# IF_Supply.net
KiCad netlist of a schematic drawn in Altium Designer
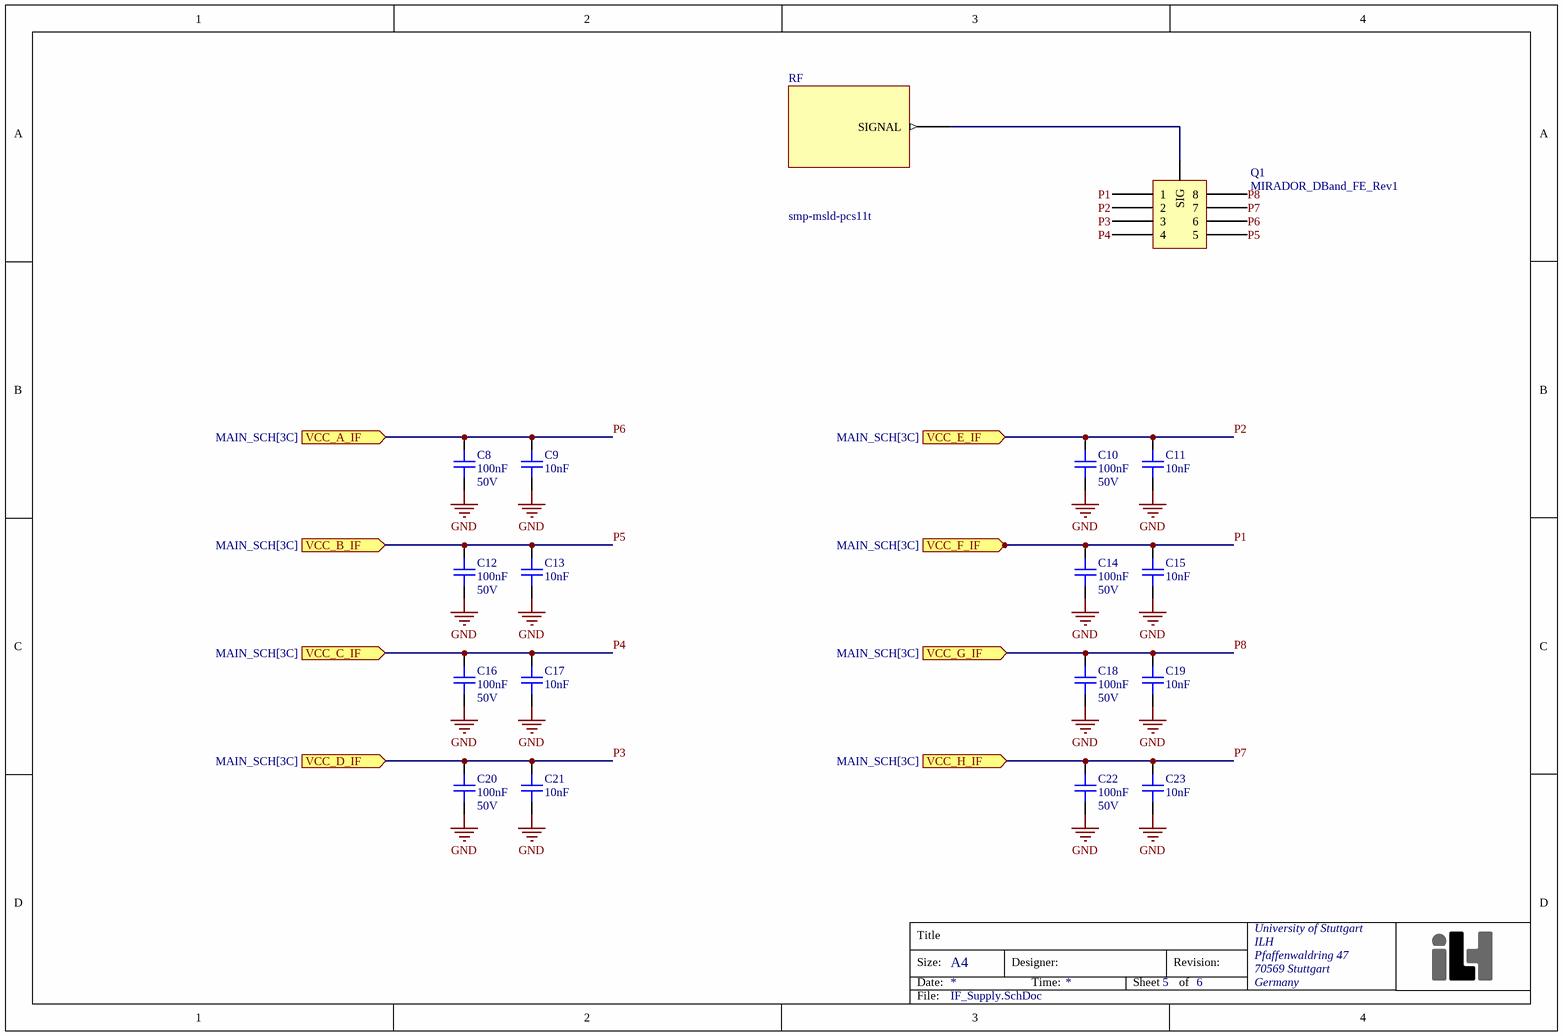
[diagram p0: IF_Supply.SchDoc]

(export (version "E")
  (design (tool "Eeschema 10.0.6"))
  (components
    (comp (ref "C8")
      (value "100nF")
      (footprint "CAPC1608X90X35LL15T15")
      (fields
        (field (name "VOLTAGE RATING") "50V")
        (field (name "TOLERANCE") "10%")
        (field (name "Comment") "06035C104KAT4A")
      )
      (libsource (lib "ILH") (part "Capacitor Voltage Rating"))
    )
    (comp (ref "C9")
      (value "10nF")
      (footprint "CAPC1050X55X23ML05T13")
      (fields (field (name "Comment") "CL05B104KO5NNNC"))
      (libsource (lib "ILH") (part "Capacitor Voltage Rating"))
    )
    (comp (ref "C10")
      (value "100nF")
      (footprint "CAPC1608X90X35LL15T15")
      (fields
        (field (name "VOLTAGE RATING") "50V")
        (field (name "TOLERANCE") "10%")
        (field (name "Comment") "06035C104KAT4A")
      )
      (libsource (lib "ILH") (part "Capacitor Voltage Rating"))
    )
    (comp (ref "C11")
      (value "10nF")
      (footprint "CAPC1050X55X23ML05T13")
      (fields (field (name "Comment") "CL05B104KO5NNNC"))
      (libsource (lib "ILH") (part "Capacitor Voltage Rating"))
    )
    (comp (ref "C12")
      (value "100nF")
      (footprint "CAPC1608X90X35LL15T15")
      (fields
        (field (name "VOLTAGE RATING") "50V")
        (field (name "TOLERANCE") "10%")
        (field (name "Comment") "06035C104KAT4A")
      )
      (libsource (lib "ILH") (part "Capacitor Voltage Rating"))
    )
    (comp (ref "C13")
      (value "10nF")
      (footprint "CAPC1050X55X23ML05T13")
      (fields (field (name "Comment") "CL05B104KO5NNNC"))
      (libsource (lib "ILH") (part "Capacitor Voltage Rating"))
    )
    (comp (ref "C14")
      (value "100nF")
      (footprint "CAPC1608X90X35LL15T15")
      (fields
        (field (name "VOLTAGE RATING") "50V")
        (field (name "TOLERANCE") "10%")
        (field (name "Comment") "06035C104KAT4A")
      )
      (libsource (lib "ILH") (part "Capacitor Voltage Rating"))
    )
    (comp (ref "C15")
      (value "10nF")
      (footprint "CAPC1050X55X23ML05T13")
      (fields (field (name "Comment") "CL05B104KO5NNNC"))
      (libsource (lib "ILH") (part "Capacitor Voltage Rating"))
    )
    (comp (ref "C16")
      (value "100nF")
      (footprint "CAPC1608X90X35LL15T15")
      (fields
        (field (name "VOLTAGE RATING") "50V")
        (field (name "TOLERANCE") "10%")
        (field (name "Comment") "06035C104KAT4A")
      )
      (libsource (lib "ILH") (part "Capacitor Voltage Rating"))
    )
    (comp (ref "C17")
      (value "10nF")
      (footprint "CAPC1050X55X23ML05T13")
      (fields (field (name "Comment") "CL05B104KO5NNNC"))
      (libsource (lib "ILH") (part "Capacitor Voltage Rating"))
    )
    (comp (ref "C18")
      (value "100nF")
      (footprint "CAPC1608X90X35LL15T15")
      (fields
        (field (name "VOLTAGE RATING") "50V")
        (field (name "TOLERANCE") "10%")
        (field (name "Comment") "06035C104KAT4A")
      )
      (libsource (lib "ILH") (part "Capacitor Voltage Rating"))
    )
    (comp (ref "C19")
      (value "10nF")
      (footprint "CAPC1050X55X23ML05T13")
      (fields (field (name "Comment") "CL05B104KO5NNNC"))
      (libsource (lib "ILH") (part "Capacitor Voltage Rating"))
    )
    (comp (ref "C20")
      (value "100nF")
      (footprint "CAPC1608X90X35LL15T15")
      (fields
        (field (name "VOLTAGE RATING") "50V")
        (field (name "TOLERANCE") "10%")
        (field (name "Comment") "06035C104KAT4A")
      )
      (libsource (lib "ILH") (part "Capacitor Voltage Rating"))
    )
    (comp (ref "C21")
      (value "10nF")
      (footprint "CAPC1050X55X23ML05T13")
      (fields (field (name "Comment") "CL05B104KO5NNNC"))
      (libsource (lib "ILH") (part "Capacitor Voltage Rating"))
    )
    (comp (ref "C22")
      (value "100nF")
      (footprint "CAPC1608X90X35LL15T15")
      (fields
        (field (name "VOLTAGE RATING") "50V")
        (field (name "TOLERANCE") "10%")
        (field (name "Comment") "06035C104KAT4A")
      )
      (libsource (lib "ILH") (part "Capacitor Voltage Rating"))
    )
    (comp (ref "C23")
      (value "10nF")
      (footprint "CAPC1050X55X23ML05T13")
      (fields (field (name "Comment") "CL05B104KO5NNNC"))
      (libsource (lib "ILH") (part "Capacitor Voltage Rating"))
    )
    (comp (ref "Q1")
      (value "MIRADOR_DBand_FE_Rev1")
      (footprint "MMIC_SMM-Footprint-1")
      (description "DC and IF bonded footprint of TWA+self-mixing mixer")
      (libsource (lib "ILH") (part "Mirador"))
    )
    (comp (ref "RF")
      (value "smp-msld-pcs11t")
      (footprint "SMP_FTP")
      (libsource (lib "ILH") (part "smp-msld"))
    )
  )
  (nets
    (net (code "1") (name "/P1") (class "Default")
      (node (ref "C14") (pin "2") (pinfunction "2_2") (pintype "passive"))
      (node (ref "C15") (pin "2") (pinfunction "2_2") (pintype "passive"))
      (node (ref "Q1") (pin "1") (pinfunction "1_1") (pintype "passive"))
    )
    (net (code "2") (name "/P2") (class "Default")
      (node (ref "C10") (pin "2") (pinfunction "2_2") (pintype "passive"))
      (node (ref "C11") (pin "2") (pinfunction "2_2") (pintype "passive"))
      (node (ref "Q1") (pin "2") (pinfunction "2_2") (pintype "passive"))
    )
    (net (code "3") (name "/P3") (class "Default")
      (node (ref "C20") (pin "2") (pinfunction "2_2") (pintype "passive"))
      (node (ref "C21") (pin "2") (pinfunction "2_2") (pintype "passive"))
      (node (ref "Q1") (pin "3") (pinfunction "3_3") (pintype "passive"))
    )
    (net (code "4") (name "/P4") (class "Default")
      (node (ref "C16") (pin "2") (pinfunction "2_2") (pintype "passive"))
      (node (ref "C17") (pin "2") (pinfunction "2_2") (pintype "passive"))
      (node (ref "Q1") (pin "4") (pinfunction "4_4") (pintype "passive"))
    )
    (net (code "5") (name "/P5") (class "Default")
      (node (ref "C12") (pin "2") (pinfunction "2_2") (pintype "passive"))
      (node (ref "C13") (pin "2") (pinfunction "2_2") (pintype "passive"))
      (node (ref "Q1") (pin "5") (pinfunction "5_5") (pintype "passive"))
    )
    (net (code "6") (name "/P6") (class "Default")
      (node (ref "C8") (pin "2") (pinfunction "2_2") (pintype "passive"))
      (node (ref "C9") (pin "2") (pinfunction "2_2") (pintype "passive"))
      (node (ref "Q1") (pin "6") (pinfunction "6_6") (pintype "passive"))
    )
    (net (code "7") (name "/P7") (class "Default")
      (node (ref "C22") (pin "2") (pinfunction "2_2") (pintype "passive"))
      (node (ref "C23") (pin "2") (pinfunction "2_2") (pintype "passive"))
      (node (ref "Q1") (pin "7") (pinfunction "7_7") (pintype "passive"))
    )
    (net (code "8") (name "/P8") (class "Default")
      (node (ref "C18") (pin "2") (pinfunction "2_2") (pintype "passive"))
      (node (ref "C19") (pin "2") (pinfunction "2_2") (pintype "passive"))
      (node (ref "Q1") (pin "8") (pinfunction "8_8") (pintype "passive"))
    )
    (net (code "9") (name "GND") (class "Default")
      (node (ref "C10") (pin "1") (pinfunction "1_1") (pintype "passive"))
      (node (ref "C11") (pin "1") (pinfunction "1_1") (pintype "passive"))
      (node (ref "C12") (pin "1") (pinfunction "1_1") (pintype "passive"))
      (node (ref "C13") (pin "1") (pinfunction "1_1") (pintype "passive"))
      (node (ref "C14") (pin "1") (pinfunction "1_1") (pintype "passive"))
      (node (ref "C15") (pin "1") (pinfunction "1_1") (pintype "passive"))
      (node (ref "C16") (pin "1") (pinfunction "1_1") (pintype "passive"))
      (node (ref "C17") (pin "1") (pinfunction "1_1") (pintype "passive"))
      (node (ref "C18") (pin "1") (pinfunction "1_1") (pintype "passive"))
      (node (ref "C19") (pin "1") (pinfunction "1_1") (pintype "passive"))
      (node (ref "C20") (pin "1") (pinfunction "1_1") (pintype "passive"))
      (node (ref "C21") (pin "1") (pinfunction "1_1") (pintype "passive"))
      (node (ref "C22") (pin "1") (pinfunction "1_1") (pintype "passive"))
      (node (ref "C23") (pin "1") (pinfunction "1_1") (pintype "passive"))
      (node (ref "C8") (pin "1") (pinfunction "1_1") (pintype "passive"))
      (node (ref "C9") (pin "1") (pinfunction "1_1") (pintype "passive"))
    )
    (net (code "10") (name "Net-(RF-SIGNAL)") (class "Default")
      (node (ref "Q1") (pin "SIG") (pinfunction "SIG_SIG") (pintype "passive"))
      (node (ref "RF") (pin "2") (pinfunction "SIGNAL_2") (pintype "output"))
    )
  )
)
